# i2c-level-shifter.net
KiCad netlist of a schematic drawn in EAGLE
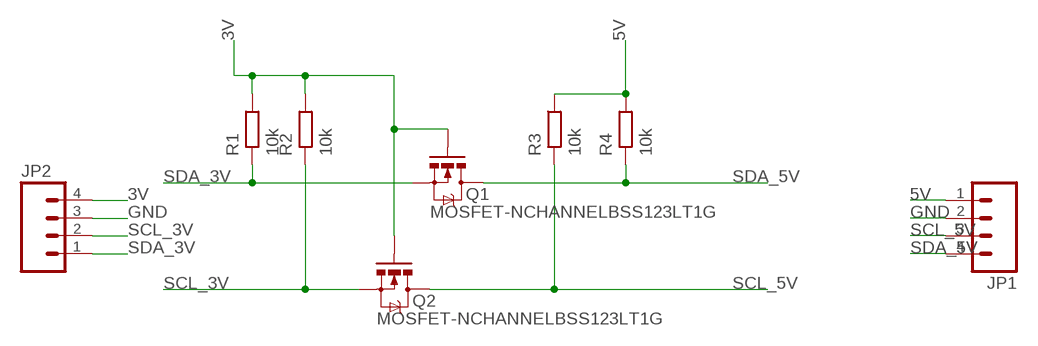
[diagram p0: schematic, sheet 1]

(export (version "E")
  (design (tool "Eeschema 10.0.6"))
  (components
    (comp (ref "JP1")
      (value "M04LOCK_LONGPADS")
      (footprint "eagle-import:1X04_LOCK_LONGPADS")
      (libsource (lib "eagle-import") (part "M04LOCK_LONGPADS"))
    )
    (comp (ref "JP2")
      (value "M04LOCK_LONGPADS")
      (footprint "eagle-import:1X04_LOCK_LONGPADS")
      (libsource (lib "eagle-import") (part "M04LOCK_LONGPADS"))
    )
    (comp (ref "Q1")
      (value "MOSFET-NCHANNELBSS123LT1G")
      (footprint "eagle-import:SOT23")
      (libsource (lib "eagle-import") (part "MOSFET-NCHANNELBSS123LT1G"))
    )
    (comp (ref "Q2")
      (value "MOSFET-NCHANNELBSS123LT1G")
      (footprint "eagle-import:SOT23")
      (libsource (lib "eagle-import") (part "MOSFET-NCHANNELBSS123LT1G"))
    )
    (comp (ref "R1")
      (value "10k")
      (footprint "eagle-import:R0603-N")
      (fields (field (name "MF") "VISHAY/DALE") (field (name "MPN") "CRCW040210K0FKED"))
      (libsource (lib "eagle-import") (part "RESISTOR0603-N"))
    )
    (comp (ref "R2")
      (value "10k")
      (footprint "eagle-import:R0603-N")
      (fields (field (name "MF") "VISHAY/DALE") (field (name "MPN") "CRCW040210K0FKED"))
      (libsource (lib "eagle-import") (part "RESISTOR0603-N"))
    )
    (comp (ref "R3")
      (value "10k")
      (footprint "eagle-import:R0603-N")
      (fields (field (name "MF") "VISHAY/DALE") (field (name "MPN") "CRCW040210K0FKED"))
      (libsource (lib "eagle-import") (part "RESISTOR0603-N"))
    )
    (comp (ref "R4")
      (value "10k")
      (footprint "eagle-import:R0603-N")
      (fields (field (name "MF") "VISHAY/DALE") (field (name "MPN") "CRCW040210K0FKED"))
      (libsource (lib "eagle-import") (part "RESISTOR0603-N"))
    )
  )
  (nets
    (net (code "1") (name "/3V") (class "Default")
      (node (ref "JP2") (pin "4") (pinfunction "4_4") (pintype "passive"))
      (node (ref "Q1") (pin "1") (pinfunction "G_1") (pintype "passive"))
      (node (ref "Q2") (pin "1") (pinfunction "G_1") (pintype "passive"))
      (node (ref "R1") (pin "2") (pinfunction "P$2_2") (pintype "passive"))
      (node (ref "R2") (pin "2") (pinfunction "P$2_2") (pintype "passive"))
    )
    (net (code "2") (name "/5V") (class "Default")
      (node (ref "JP1") (pin "1") (pinfunction "1_1") (pintype "passive"))
      (node (ref "R3") (pin "2") (pinfunction "P$2_2") (pintype "passive"))
      (node (ref "R4") (pin "2") (pinfunction "P$2_2") (pintype "passive"))
    )
    (net (code "3") (name "/GND") (class "Default")
      (node (ref "JP1") (pin "2") (pinfunction "2_2") (pintype "passive"))
      (node (ref "JP2") (pin "3") (pinfunction "3_3") (pintype "passive"))
    )
    (net (code "4") (name "/SCL_3V") (class "Default")
      (node (ref "JP2") (pin "2") (pinfunction "2_2") (pintype "passive"))
      (node (ref "Q2") (pin "2") (pinfunction "S_2") (pintype "passive"))
      (node (ref "R2") (pin "1") (pinfunction "P$1_1") (pintype "passive"))
    )
    (net (code "5") (name "/SCL_5V") (class "Default")
      (node (ref "JP1") (pin "3") (pinfunction "3_3") (pintype "passive"))
      (node (ref "Q2") (pin "3") (pinfunction "D_3") (pintype "passive"))
      (node (ref "R3") (pin "1") (pinfunction "P$1_1") (pintype "passive"))
    )
    (net (code "6") (name "/SDA_3V") (class "Default")
      (node (ref "JP2") (pin "1") (pinfunction "1_1") (pintype "passive"))
      (node (ref "Q1") (pin "2") (pinfunction "S_2") (pintype "passive"))
      (node (ref "R1") (pin "1") (pinfunction "P$1_1") (pintype "passive"))
    )
    (net (code "7") (name "/SDA_5V") (class "Default")
      (node (ref "JP1") (pin "4") (pinfunction "4_4") (pintype "passive"))
      (node (ref "Q1") (pin "3") (pinfunction "D_3") (pintype "passive"))
      (node (ref "R4") (pin "1") (pinfunction "P$1_1") (pintype "passive"))
    )
  )
)
